# USB_SWITCH.net
KiCad netlist of a schematic drawn in Altium Designer
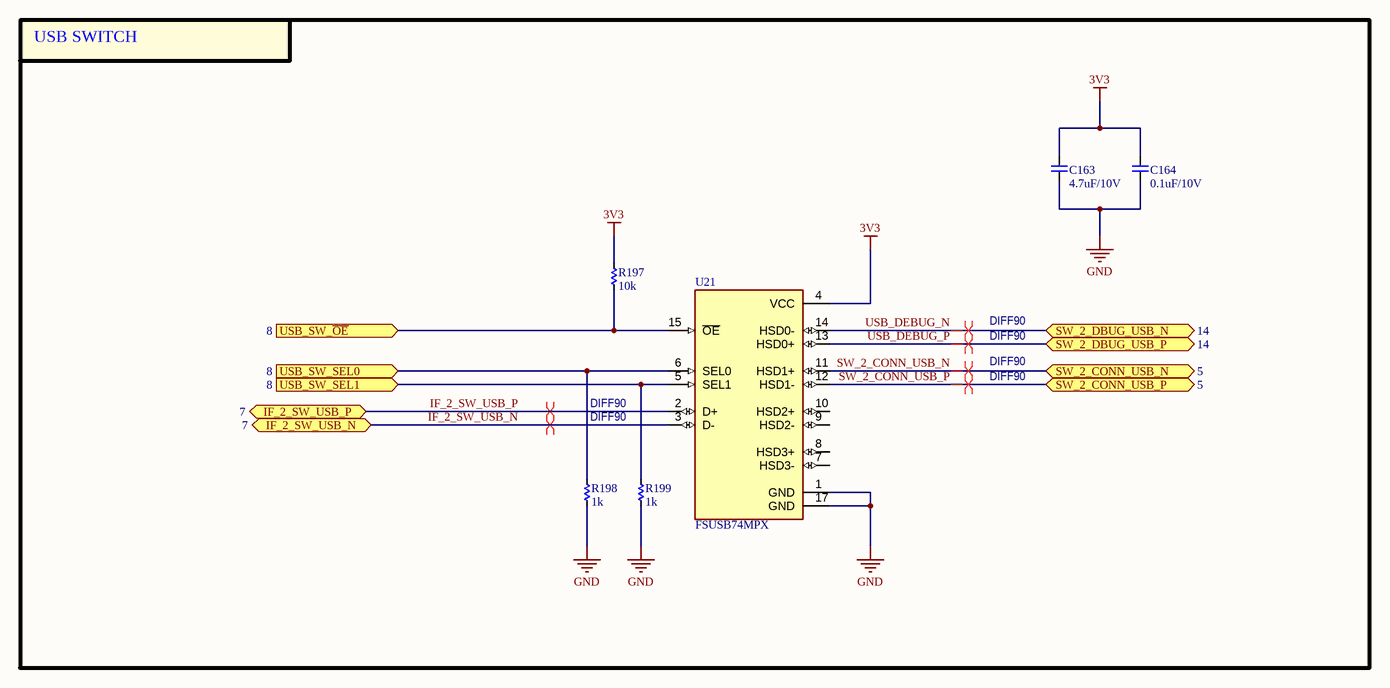
[diagram p0: USB_SWITCH.SchDoc]

(export (version "E")
  (design (tool "Eeschema 10.0.6"))
  (components
    (comp (ref "C163")
      (value "4.7uF/10V")
      (footprint "CAP_C_1005X50_L")
      (description "CAP CHIP")
      (libsource (lib "IFBschelib") (part "_CAP_C_2"))
    )
    (comp (ref "C164")
      (value "0.1uF/10V")
      (footprint "CAP_C_1005X50_L")
      (description "CAP CHIP")
      (libsource (lib "IFBschelib") (part "_CAP_C_2"))
    )
    (comp (ref "R197")
      (value "10k")
      (footprint "RES_C_1005x30_L")
      (description "RES")
      (libsource (lib "IFBschelib") (part "_RES_B_2"))
    )
    (comp (ref "R198")
      (value "1k")
      (footprint "RES_C_1005x30_L")
      (description "RES")
      (libsource (lib "IFBschelib") (part "_RES_B_2"))
    )
    (comp (ref "R199")
      (value "1k")
      (footprint "RES_C_1005x30_L")
      (description "RES")
      (libsource (lib "IFBschelib") (part "_RES_B_2"))
    )
    (comp (ref "U21")
      (value "FSUSB74MPX")
      (footprint "QFN50P300X300X80-17N")
      (description "USB Switch IC 1 Channel 16-MLP (3x3)")
      (fields (field (name "MF") "ON Semiconductor"))
      (libsource (lib "IFBschelib") (part "IC_USB_SW_FSUSB74MPX"))
    )
  )
  (nets
    (net (code "1") (name "/IF_2_SW_USB_N") (class "Default")
      (node (ref "U21") (pin "3") (pinfunction "D-_3") (pintype "bidirectional"))
    )
    (net (code "2") (name "/IF_2_SW_USB_P") (class "Default")
      (node (ref "U21") (pin "2") (pinfunction "D+_2") (pintype "bidirectional"))
    )
    (net (code "3") (name "/SW_2_CONN_USB_N") (class "Default")
      (node (ref "U21") (pin "11") (pinfunction "HSD1+_11") (pintype "bidirectional"))
    )
    (net (code "4") (name "/SW_2_CONN_USB_P") (class "Default")
      (node (ref "U21") (pin "12") (pinfunction "HSD1-_12") (pintype "bidirectional"))
    )
    (net (code "5") (name "/USB_DEBUG_N") (class "Default")
      (node (ref "U21") (pin "14") (pinfunction "HSD0-_14") (pintype "bidirectional"))
    )
    (net (code "6") (name "/USB_DEBUG_P") (class "Default")
      (node (ref "U21") (pin "13") (pinfunction "HSD0+_13") (pintype "bidirectional"))
    )
    (net (code "7") (name "/USB_SW_SEL0") (class "Default")
      (node (ref "R198") (pin "2") (pinfunction "2_2") (pintype "passive"))
      (node (ref "U21") (pin "6") (pinfunction "SEL0_6") (pintype "input"))
    )
    (net (code "8") (name "/USB_SW_SEL1") (class "Default")
      (node (ref "R199") (pin "2") (pinfunction "2_2") (pintype "passive"))
      (node (ref "U21") (pin "5") (pinfunction "SEL1_5") (pintype "input"))
    )
    (net (code "9") (name "/USB_SW_~{OE}") (class "Default")
      (node (ref "R197") (pin "1") (pinfunction "1_1") (pintype "passive"))
      (node (ref "U21") (pin "15") (pinfunction "~{OE}_15") (pintype "input"))
    )
    (net (code "10") (name "3V3") (class "Default")
      (node (ref "C163") (pin "2") (pinfunction "2_2") (pintype "passive"))
      (node (ref "C164") (pin "2") (pinfunction "2_2") (pintype "passive"))
      (node (ref "R197") (pin "2") (pinfunction "2_2") (pintype "passive"))
      (node (ref "U21") (pin "4") (pinfunction "VCC_4") (pintype "power_in"))
    )
    (net (code "11") (name "GND") (class "Default")
      (node (ref "C163") (pin "1") (pinfunction "1_1") (pintype "passive"))
      (node (ref "C164") (pin "1") (pinfunction "1_1") (pintype "passive"))
      (node (ref "R198") (pin "1") (pinfunction "1_1") (pintype "passive"))
      (node (ref "R199") (pin "1") (pinfunction "1_1") (pintype "passive"))
      (node (ref "U21") (pin "1") (pinfunction "GND_1") (pintype "power_in"))
      (node (ref "U21") (pin "17") (pinfunction "GND_17") (pintype "power_in"))
    )
    (net (code "12") (name "unconnected-(U21-HSD2+-Pad10)") (class "Default")
      (node (ref "U21") (pin "10") (pinfunction "HSD2+_10") (pintype "bidirectional"))
    )
    (net (code "13") (name "unconnected-(U21-HSD2--Pad9)") (class "Default")
      (node (ref "U21") (pin "9") (pinfunction "HSD2-_9") (pintype "bidirectional"))
    )
    (net (code "14") (name "unconnected-(U21-HSD3+-Pad8)") (class "Default")
      (node (ref "U21") (pin "8") (pinfunction "HSD3+_8") (pintype "bidirectional"))
    )
    (net (code "15") (name "unconnected-(U21-HSD3--Pad7)") (class "Default")
      (node (ref "U21") (pin "7") (pinfunction "HSD3-_7") (pintype "bidirectional"))
    )
  )
)
